# ECG_PWR_MGMT.net
KiCad netlist of a schematic drawn in Altium Designer
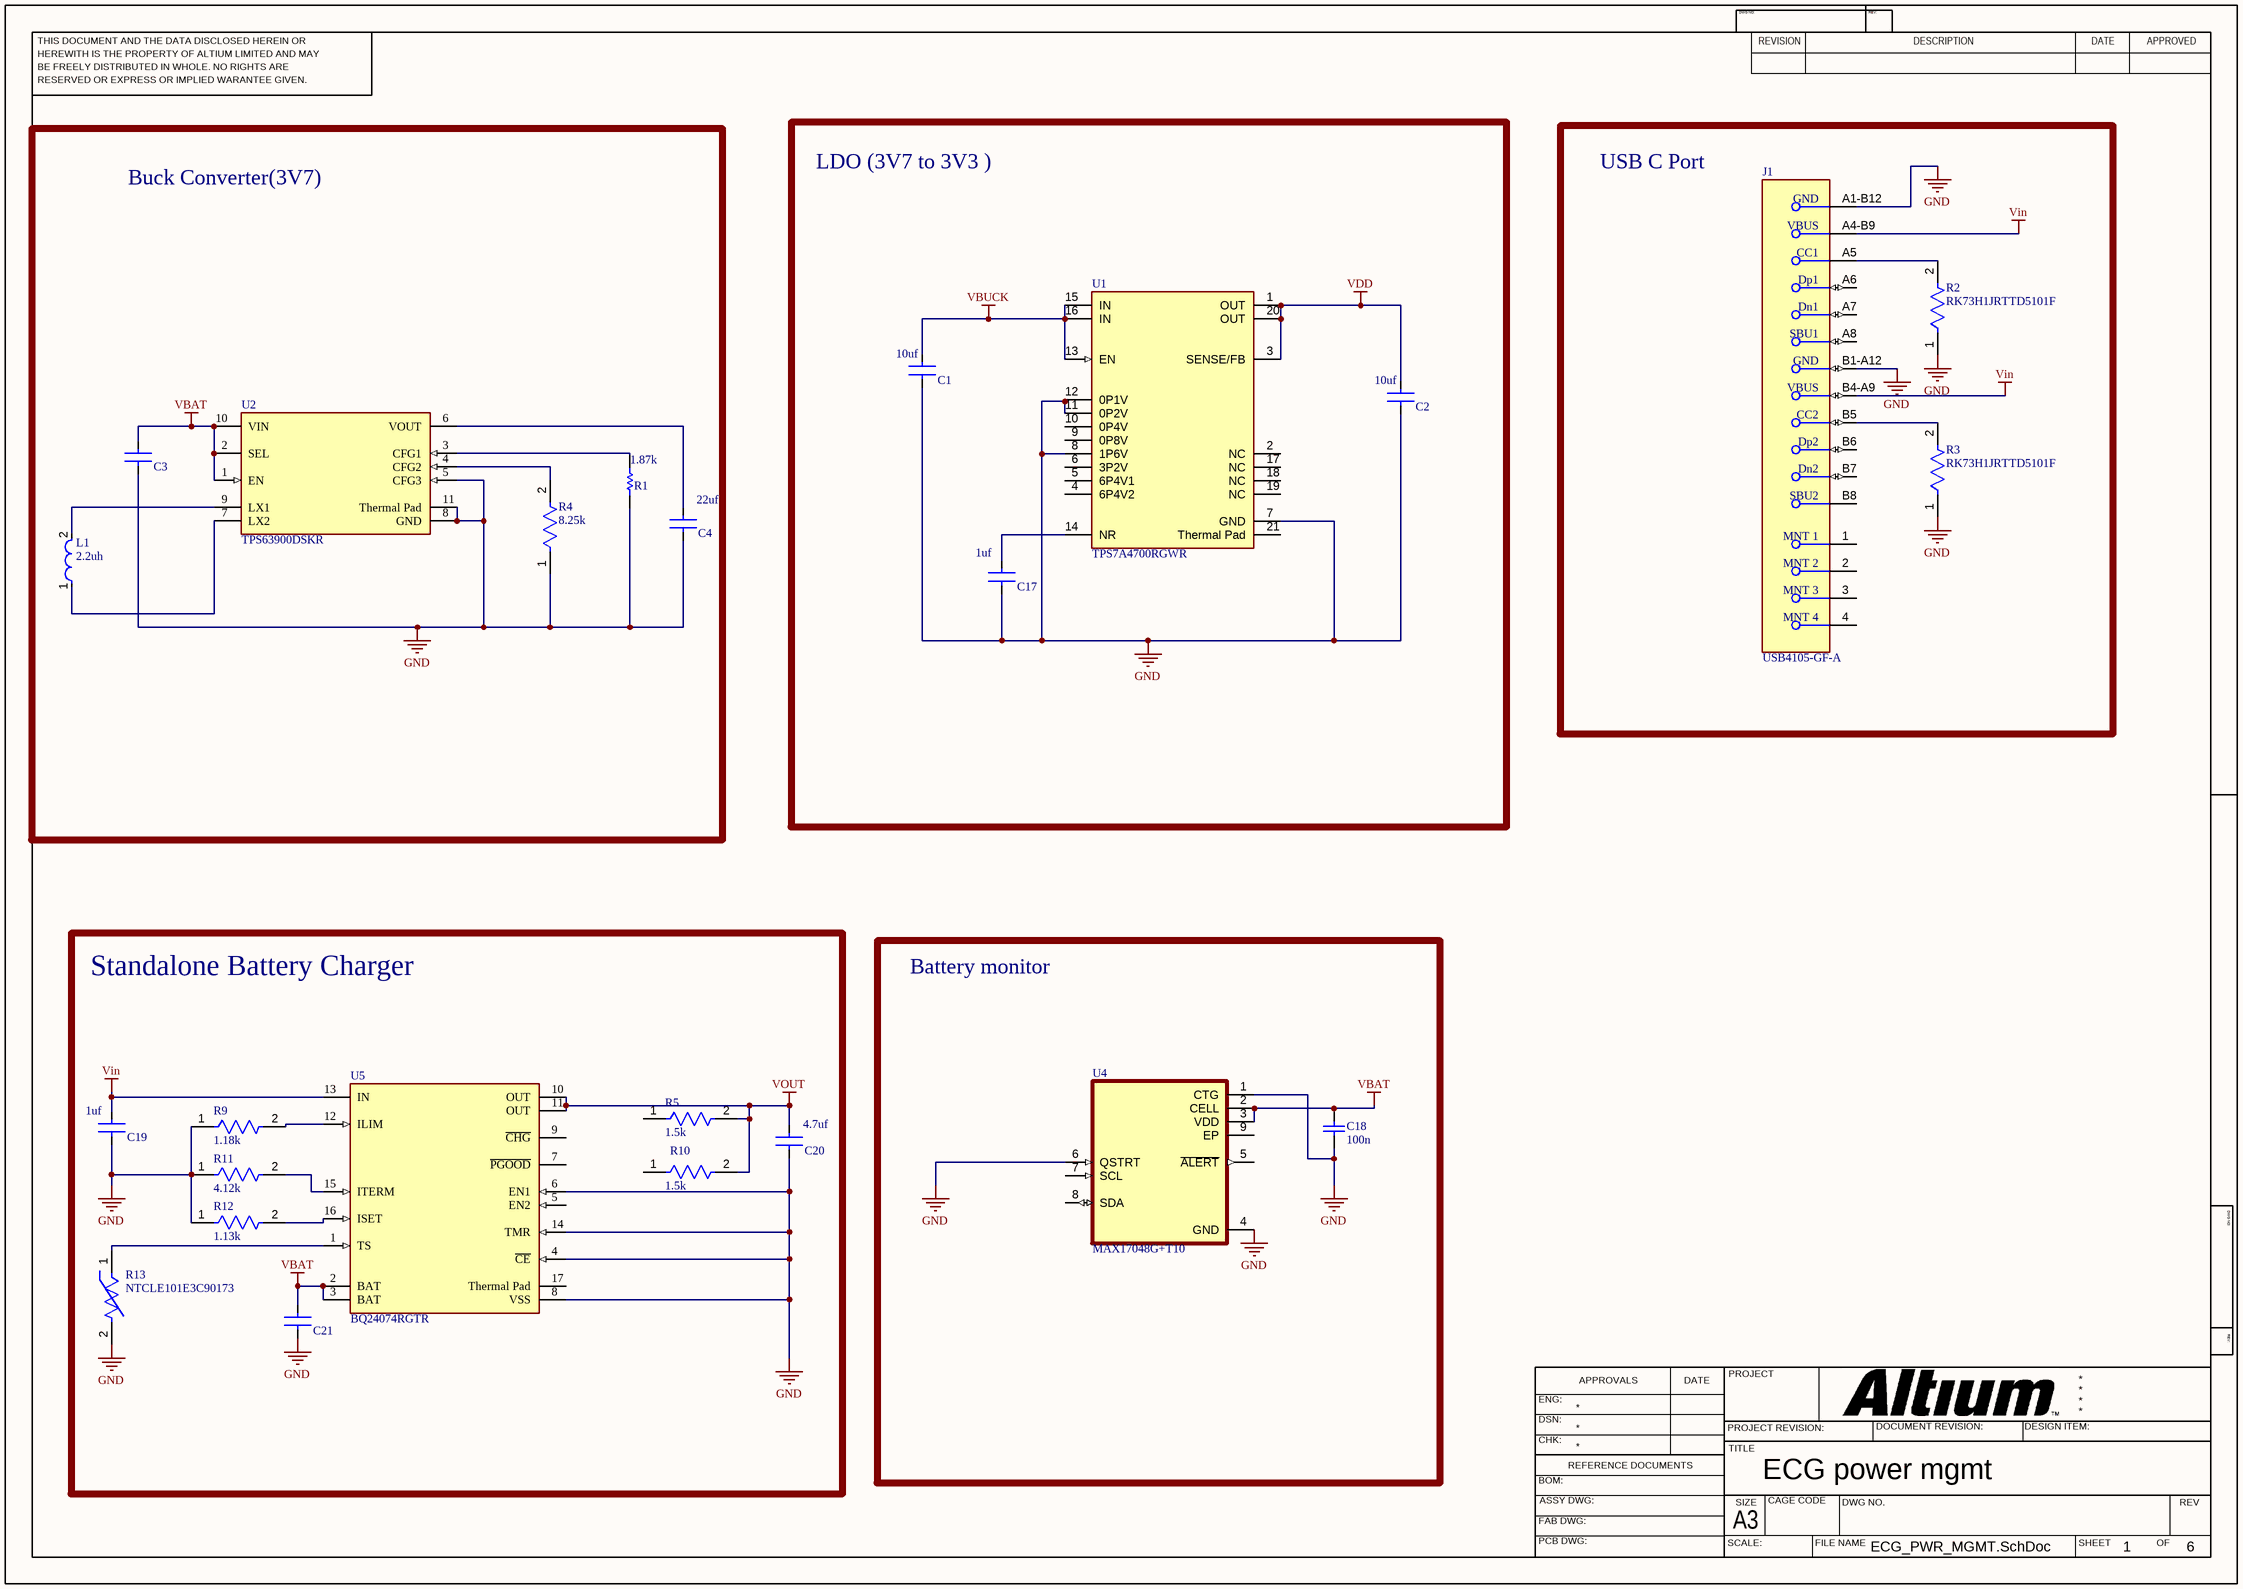
[diagram p0: ECG_PWR_MGMT.SchDoc]

(export (version "E")
  (design (tool "Eeschema 10.0.6"))
  (components
    (comp (ref "C1") (value "10uf") (libsource (lib "ecg_device_components") (part "CAP-0805-16V-SMD-IPC_A")))
    (comp (ref "C2") (value "10uf") (libsource (lib "ecg_device_components") (part "CAP-0805-16V-SMD-IPC_A")))
    (comp (ref "C3")
      (value "Template for SMD cap")
      (libsource (lib "ecg_device_components") (part "CAP-0805-16V-SMD-IPC_A"))
    )
    (comp (ref "C4") (value "22uf") (libsource (lib "ecg_device_components") (part "CAP-0805-16V-SMD-IPC_A")))
    (comp (ref "C17") (value "1uf") (libsource (lib "ecg_device_components") (part "CAP-0805-16V-SMD-IPC_A")))
    (comp (ref "C18")
      (value "100n")
      (footprint "CAP_SMD_0603_IPC_A")
      (fields
        (field (name "MANUFACTURER") "AVX Interconnect / Elco")
        (field (name "PART NUMBER") "0603ZC103MAT2A")
      )
      (libsource (lib "ecg_device_components") (part "CAP-0603-16V-SMD"))
    )
    (comp (ref "C19") (value "1uf") (libsource (lib "ecg_device_components") (part "CAP-0805-16V-SMD-IPC_A")))
    (comp (ref "C20")
      (value "4.7uf")
      (libsource (lib "ecg_device_components") (part "CAP-0805-16V-SMD-IPC_A"))
    )
    (comp (ref "C21")
      (value "Template for SMD cap")
      (libsource (lib "ecg_device_components") (part "CAP-0805-16V-SMD-IPC_A"))
    )
    (comp (ref "J1")
      (value "USB4105-GF-A")
      (footprint "FP-USB4105-GF-A-MFG")
      (description "CONN RCPT USB2.0 TYPEC 5A")
      (fields
        (field (name "MANUFACTURER") "GCT")
        (field (name "OCTOPART") "https://octopart.com/usb4105-gf-a-gct-106627878")
      )
      (libsource (lib "Altium Content Vault") (part "e7c17a616881a82b79941196b4bec10"))
    )
    (comp (ref "L1")
      (value "2.2uh")
      (footprint "FP-LQM2HPN_G0-IPC_C")
      (description "Multilayer Type Inductor for Power Lines, 1008 (2520), 2.2μH, 20%, 0.1Ω, 1.3A")
      (fields (field (name "TOLERANCE") "20%"))
      (libsource (lib "Altium Content Vault") (part "725321dda6339637d4d059423bc1c3c"))
    )
    (comp (ref "R1")
      (value "1.87k")
      (footprint "RESC2013X60X35ML10T20")
      (libsource (lib "ecg_device_components") (part "1K 0805"))
    )
    (comp (ref "R2")
      (value "RK73H1JRTTD5101F")
      (footprint "FP-RK73H1J-IPC_C")
      (description "5.1kΩ ±1% 0.1W Chip Resistor 0603 Flat Chip (Anti-Sulfuration) AEC-Q200 Qualified")
      (fields (field (name "TOLERANCE") "1%"))
      (libsource (lib "Altium Content Vault") (part "1029c3af85768c4190bb7ad29bc67b5"))
    )
    (comp (ref "R3")
      (value "RK73H1JRTTD5101F")
      (footprint "FP-RK73H1J-IPC_C")
      (description "5.1kΩ ±1% 0.1W Chip Resistor 0603 Flat Chip (Anti-Sulfuration) AEC-Q200 Qualified")
      (fields (field (name "TOLERANCE") "1%"))
      (libsource (lib "Altium Content Vault") (part "1029c3af85768c4190bb7ad29bc67b5"))
    )
    (comp (ref "R4")
      (value "8.25k")
      (footprint "FP-MCT0603-IPC_B")
      (description "RES SMD 100 OHM 1% 1/8W 0603")
      (libsource (lib "Altium Content Vault") (part "1029c3af85768c4190bb7ad29bc67b5"))
    )
    (comp (ref "R5")
      (value "1.5k")
      (footprint "FP-MCT0603-IPC_B")
      (description "RES SMD 100 OHM 1% 1/8W 0603")
      (libsource (lib "Altium Content Vault") (part "1029c3af85768c4190bb7ad29bc67b5"))
    )
    (comp (ref "R9")
      (value "1.18k")
      (footprint "FP-MCT0603-IPC_B")
      (description "RES SMD 100 OHM 1% 1/8W 0603")
      (libsource (lib "Altium Content Vault") (part "1029c3af85768c4190bb7ad29bc67b5"))
    )
    (comp (ref "R10")
      (value "1.5k")
      (footprint "FP-MCT0603-IPC_B")
      (description "RES SMD 100 OHM 1% 1/8W 0603")
      (libsource (lib "Altium Content Vault") (part "1029c3af85768c4190bb7ad29bc67b5"))
    )
    (comp (ref "R11")
      (value "4.12k")
      (footprint "FP-MCT0603-IPC_B")
      (description "RES SMD 100 OHM 1% 1/8W 0603")
      (libsource (lib "Altium Content Vault") (part "1029c3af85768c4190bb7ad29bc67b5"))
    )
    (comp (ref "R12")
      (value "1.13k")
      (footprint "FP-MCT0603-IPC_B")
      (description "RES SMD 100 OHM 1% 1/8W 0603")
      (libsource (lib "Altium Content Vault") (part "1029c3af85768c4190bb7ad29bc67b5"))
    )
    (comp (ref "R13")
      (value "NTCLE101E3C90173")
      (footprint "FP-NTCLE101E3C90173-MFG")
      (description "THERM NTC 10KOHM 3435K RADIAL")
      (fields (field (name "TOLERANCE") "1%"))
      (libsource (lib "Altium Content Vault") (part "3b148a6ebabc5fb4d708a66c052d352"))
    )
    (comp (ref "U1")
      (value "TPS7A4700RGWR")
      (footprint "FP-RGW0020A-MFG")
      (description "IC REG LINEAR POS ADJ 1A 20VQFN")
      (fields
        (field (name "OCTOPART") "https://octopart.com/tps7a4700rgwr-texas+instruments-21221956")
        (field (name "MANUFACTURER") "Texas Instruments")
      )
      (libsource (lib "Altium Content Vault") (part "8e99b082ac9f85253ef2256b190b767"))
    )
    (comp (ref "U2")
      (value "TPS63900DSKR")
      (footprint "FP-DSK0010A-IPC_C")
      (description "1.8-V TO 5.5-V, 75-NA IQ BUCK-BO")
      (libsource (lib "Altium Content Vault") (part "087cbe63ebfe39a16d3bf11a348b5dd"))
    )
    (comp (ref "U4")
      (value "MAX17048G+T10")
      (footprint "max17048g+t10")
      (description "3ÂµA 1-Cell/2-Cell Fuel Gauge with ModelGauge")
      (fields (field (name "MF") "Analog Devices"))
      (libsource (lib "ecg_device_components") (part "MAX17048G+T10"))
    )
    (comp (ref "U5")
      (value "BQ24074RGTR")
      (footprint "FP-RGT0016C-IPC_B")
      (description "IC LI-ION CHARGE MGMT 16-QFN")
      (libsource (lib "Altium Content Vault") (part "bc0294d1c007ba64400ebcffad863a1"))
    )
  )
  (nets
    (net (code "1") (name "GND") (class "Default")
      (node (ref "C1") (pin "1") (pinfunction "1_1") (pintype "passive"))
      (node (ref "C17") (pin "1") (pinfunction "1_1") (pintype "passive"))
      (node (ref "C18") (pin "1") (pinfunction "1_1") (pintype "passive"))
      (node (ref "C19") (pin "1") (pinfunction "1_1") (pintype "passive"))
      (node (ref "C2") (pin "1") (pinfunction "1_1") (pintype "passive"))
      (node (ref "C20") (pin "1") (pinfunction "1_1") (pintype "passive"))
      (node (ref "C21") (pin "1") (pinfunction "1_1") (pintype "passive"))
      (node (ref "C3") (pin "1") (pinfunction "1_1") (pintype "passive"))
      (node (ref "C4") (pin "1") (pinfunction "1_1") (pintype "passive"))
      (node (ref "J1") (pin "A1-B12") (pinfunction "GND_A1-B12") (pintype "power_in"))
      (node (ref "J1") (pin "B1-A12") (pinfunction "GND_B1-A12") (pintype "bidirectional"))
      (node (ref "R1") (pin "1") (pinfunction "1_1") (pintype "passive"))
      (node (ref "R11") (pin "1") (pinfunction "1_1") (pintype "passive"))
      (node (ref "R12") (pin "1") (pinfunction "1_1") (pintype "passive"))
      (node (ref "R13") (pin "2") (pinfunction "2_2") (pintype "passive"))
      (node (ref "R2") (pin "1") (pinfunction "1_1") (pintype "passive"))
      (node (ref "R3") (pin "1") (pinfunction "1_1") (pintype "passive"))
      (node (ref "R4") (pin "1") (pinfunction "1_1") (pintype "passive"))
      (node (ref "R9") (pin "1") (pinfunction "1_1") (pintype "passive"))
      (node (ref "U1") (pin "11") (pinfunction "0P2V_11") (pintype "passive"))
      (node (ref "U1") (pin "12") (pinfunction "0P1V_12") (pintype "passive"))
      (node (ref "U1") (pin "7") (pinfunction "GND_7") (pintype "power_in"))
      (node (ref "U1") (pin "8") (pinfunction "1P6V_8") (pintype "passive"))
      (node (ref "U2") (pin "11") (pinfunction "Thermal_Pad_11") (pintype "power_in"))
      (node (ref "U2") (pin "5") (pinfunction "CFG3_5") (pintype "input"))
      (node (ref "U2") (pin "8") (pinfunction "GND_8") (pintype "power_in"))
      (node (ref "U4") (pin "1") (pinfunction "CTG_1") (pintype "power_in"))
      (node (ref "U4") (pin "4") (pinfunction "GND_4") (pintype "power_in"))
      (node (ref "U4") (pin "6") (pinfunction "QSTRT_6") (pintype "input"))
      (node (ref "U5") (pin "14") (pinfunction "TMR_14") (pintype "input"))
      (node (ref "U5") (pin "4") (pinfunction "~{CE}_4") (pintype "input"))
      (node (ref "U5") (pin "6") (pinfunction "EN1_6") (pintype "input"))
      (node (ref "U5") (pin "8") (pinfunction "VSS_8") (pintype "power_in"))
    )
    (net (code "2") (name "Net-(J1-CC1)") (class "Default")
      (node (ref "J1") (pin "A5") (pinfunction "CC1_A5") (pintype "power_in"))
      (node (ref "R2") (pin "2") (pinfunction "2_2") (pintype "passive"))
    )
    (net (code "3") (name "Net-(J1-CC2)") (class "Default")
      (node (ref "J1") (pin "B5") (pinfunction "CC2_B5") (pintype "bidirectional"))
      (node (ref "R3") (pin "2") (pinfunction "2_2") (pintype "passive"))
    )
    (net (code "4") (name "Net-(U1-NR)") (class "Default")
      (node (ref "C17") (pin "2") (pinfunction "2_2") (pintype "passive"))
      (node (ref "U1") (pin "14") (pinfunction "NR_14") (pintype "passive"))
    )
    (net (code "5") (name "Net-(U2-CFG1)") (class "Default")
      (node (ref "R1") (pin "2") (pinfunction "2_2") (pintype "passive"))
      (node (ref "U2") (pin "3") (pinfunction "CFG1_3") (pintype "input"))
    )
    (net (code "6") (name "Net-(U2-CFG2)") (class "Default")
      (node (ref "R4") (pin "2") (pinfunction "2_2") (pintype "passive"))
      (node (ref "U2") (pin "4") (pinfunction "CFG2_4") (pintype "input"))
    )
    (net (code "7") (name "Net-(U2-LX1)") (class "Default")
      (node (ref "L1") (pin "2") (pinfunction "2_2") (pintype "passive"))
      (node (ref "U2") (pin "9") (pinfunction "LX1_9") (pintype "passive"))
    )
    (net (code "8") (name "Net-(U2-LX2)") (class "Default")
      (node (ref "L1") (pin "1") (pinfunction "1_1") (pintype "passive"))
      (node (ref "U2") (pin "7") (pinfunction "LX2_7") (pintype "passive"))
    )
    (net (code "9") (name "Net-(U2-VOUT)") (class "Default")
      (node (ref "C4") (pin "2") (pinfunction "2_2") (pintype "passive"))
      (node (ref "U2") (pin "6") (pinfunction "VOUT_6") (pintype "passive"))
    )
    (net (code "10") (name "Net-(U5-ILIM)") (class "Default")
      (node (ref "R9") (pin "2") (pinfunction "2_2") (pintype "passive"))
      (node (ref "U5") (pin "12") (pinfunction "ILIM_12") (pintype "input"))
    )
    (net (code "11") (name "Net-(U5-ISET)") (class "Default")
      (node (ref "R12") (pin "2") (pinfunction "2_2") (pintype "passive"))
      (node (ref "U5") (pin "16") (pinfunction "ISET_16") (pintype "input"))
    )
    (net (code "12") (name "Net-(U5-ITERM)") (class "Default")
      (node (ref "R11") (pin "2") (pinfunction "2_2") (pintype "passive"))
      (node (ref "U5") (pin "15") (pinfunction "ITERM_15") (pintype "input"))
    )
    (net (code "13") (name "Net-(U5-TS)") (class "Default")
      (node (ref "R13") (pin "1") (pinfunction "1_1") (pintype "passive"))
      (node (ref "U5") (pin "1") (pinfunction "TS_1") (pintype "input"))
    )
    (net (code "14") (name "VBAT") (class "Default")
      (node (ref "C18") (pin "2") (pinfunction "2_2") (pintype "passive"))
      (node (ref "C21") (pin "2") (pinfunction "2_2") (pintype "passive"))
      (node (ref "C3") (pin "2") (pinfunction "2_2") (pintype "passive"))
      (node (ref "U2") (pin "1") (pinfunction "EN_1") (pintype "input"))
      (node (ref "U2") (pin "10") (pinfunction "VIN_10") (pintype "power_in"))
      (node (ref "U2") (pin "2") (pinfunction "SEL_2") (pintype "passive"))
      (node (ref "U4") (pin "2") (pinfunction "CELL_2") (pintype "power_in"))
      (node (ref "U4") (pin "3") (pinfunction "VDD_3") (pintype "power_in"))
      (node (ref "U5") (pin "2") (pinfunction "BAT_2") (pintype "power_in"))
      (node (ref "U5") (pin "3") (pinfunction "BAT_3") (pintype "power_in"))
    )
    (net (code "15") (name "VBUCK") (class "Default")
      (node (ref "C1") (pin "2") (pinfunction "2_2") (pintype "passive"))
      (node (ref "U1") (pin "13") (pinfunction "EN_13") (pintype "input"))
      (node (ref "U1") (pin "15") (pinfunction "IN_15") (pintype "power_in"))
      (node (ref "U1") (pin "16") (pinfunction "IN_16") (pintype "power_in"))
    )
    (net (code "16") (name "VDD") (class "Default")
      (node (ref "C2") (pin "2") (pinfunction "2_2") (pintype "passive"))
      (node (ref "U1") (pin "1") (pinfunction "OUT_1") (pintype "power_in"))
      (node (ref "U1") (pin "20") (pinfunction "OUT_20") (pintype "power_in"))
      (node (ref "U1") (pin "3") (pinfunction "SENSE/FB_3") (pintype "passive"))
    )
    (net (code "17") (name "VOUT") (class "Default")
      (node (ref "C20") (pin "2") (pinfunction "2_2") (pintype "passive"))
      (node (ref "R10") (pin "2") (pinfunction "2_2") (pintype "passive"))
      (node (ref "R5") (pin "2") (pinfunction "2_2") (pintype "passive"))
      (node (ref "U5") (pin "10") (pinfunction "OUT_10") (pintype "power_in"))
      (node (ref "U5") (pin "11") (pinfunction "OUT_11") (pintype "power_in"))
    )
    (net (code "18") (name "Vin") (class "Default")
      (node (ref "C19") (pin "2") (pinfunction "2_2") (pintype "passive"))
      (node (ref "J1") (pin "A4-B9") (pinfunction "VBUS_A4-B9") (pintype "power_in"))
      (node (ref "J1") (pin "B4-A9") (pinfunction "VBUS_B4-A9") (pintype "bidirectional"))
      (node (ref "U5") (pin "13") (pinfunction "IN_13") (pintype "power_in"))
    )
    (net (code "19") (name "unconnected-(J1-Dn1-PadA7)") (class "Default")
      (node (ref "J1") (pin "A7") (pinfunction "Dn1_A7") (pintype "bidirectional"))
    )
    (net (code "20") (name "unconnected-(J1-Dn2-PadB7)") (class "Default")
      (node (ref "J1") (pin "B7") (pinfunction "Dn2_B7") (pintype "bidirectional"))
    )
    (net (code "21") (name "unconnected-(J1-Dp1-PadA6)") (class "Default")
      (node (ref "J1") (pin "A6") (pinfunction "Dp1_A6") (pintype "bidirectional"))
    )
    (net (code "22") (name "unconnected-(J1-Dp2-PadB6)") (class "Default")
      (node (ref "J1") (pin "B6") (pinfunction "Dp2_B6") (pintype "bidirectional"))
    )
    (net (code "23") (name "unconnected-(J1-MNT_1-Pad1)") (class "Default")
      (node (ref "J1") (pin "1") (pinfunction "MNT_1_1") (pintype "power_in"))
    )
    (net (code "24") (name "unconnected-(J1-MNT_2-Pad2)") (class "Default")
      (node (ref "J1") (pin "2") (pinfunction "MNT_2_2") (pintype "power_in"))
    )
    (net (code "25") (name "unconnected-(J1-MNT_3-Pad3)") (class "Default")
      (node (ref "J1") (pin "3") (pinfunction "MNT_3_3") (pintype "power_in"))
    )
    (net (code "26") (name "unconnected-(J1-MNT_4-Pad4)") (class "Default")
      (node (ref "J1") (pin "4") (pinfunction "MNT_4_4") (pintype "power_in"))
    )
    (net (code "27") (name "unconnected-(J1-SBU1-PadA8)") (class "Default")
      (node (ref "J1") (pin "A8") (pinfunction "SBU1_A8") (pintype "bidirectional"))
    )
    (net (code "28") (name "unconnected-(J1-SBU2-PadB8)") (class "Default")
      (node (ref "J1") (pin "B8") (pinfunction "SBU2_B8") (pintype "power_in"))
    )
    (net (code "29") (name "unconnected-(R5-Pad1)") (class "Default")
      (node (ref "R5") (pin "1") (pinfunction "1_1") (pintype "passive"))
    )
    (net (code "30") (name "unconnected-(R10-Pad1)") (class "Default")
      (node (ref "R10") (pin "1") (pinfunction "1_1") (pintype "passive"))
    )
    (net (code "31") (name "unconnected-(U1-0P4V-Pad10)") (class "Default")
      (node (ref "U1") (pin "10") (pinfunction "0P4V_10") (pintype "passive"))
    )
    (net (code "32") (name "unconnected-(U1-0P8V-Pad9)") (class "Default")
      (node (ref "U1") (pin "9") (pinfunction "0P8V_9") (pintype "passive"))
    )
    (net (code "33") (name "unconnected-(U1-3P2V-Pad6)") (class "Default")
      (node (ref "U1") (pin "6") (pinfunction "3P2V_6") (pintype "passive"))
    )
    (net (code "34") (name "unconnected-(U1-6P4V1-Pad5)") (class "Default")
      (node (ref "U1") (pin "5") (pinfunction "6P4V1_5") (pintype "passive"))
    )
    (net (code "35") (name "unconnected-(U1-6P4V2-Pad4)") (class "Default")
      (node (ref "U1") (pin "4") (pinfunction "6P4V2_4") (pintype "passive"))
    )
    (net (code "36") (name "unconnected-(U1-NC-Pad2)") (class "Default")
      (node (ref "U1") (pin "2") (pinfunction "NC_2") (pintype "passive"))
    )
    (net (code "37") (name "unconnected-(U1-NC-Pad17)") (class "Default")
      (node (ref "U1") (pin "17") (pinfunction "NC_17") (pintype "passive"))
    )
    (net (code "38") (name "unconnected-(U1-NC-Pad18)") (class "Default")
      (node (ref "U1") (pin "18") (pinfunction "NC_18") (pintype "passive"))
    )
    (net (code "39") (name "unconnected-(U1-NC-Pad19)") (class "Default")
      (node (ref "U1") (pin "19") (pinfunction "NC_19") (pintype "passive"))
    )
    (net (code "40") (name "unconnected-(U1-Thermal_Pad-Pad21)") (class "Default")
      (node (ref "U1") (pin "21") (pinfunction "Thermal_Pad_21") (pintype "power_in"))
    )
    (net (code "41") (name "unconnected-(U4-EP-Pad9)") (class "Default")
      (node (ref "U4") (pin "9") (pinfunction "EP_9") (pintype "power_in"))
    )
    (net (code "42") (name "unconnected-(U4-SCL-Pad7)") (class "Default")
      (node (ref "U4") (pin "7") (pinfunction "SCL_7") (pintype "input"))
    )
    (net (code "43") (name "unconnected-(U4-SDA-Pad8)") (class "Default")
      (node (ref "U4") (pin "8") (pinfunction "SDA_8") (pintype "bidirectional"))
    )
    (net (code "44") (name "unconnected-(U4-~{ALERT}-Pad5)") (class "Default")
      (node (ref "U4") (pin "5") (pinfunction "~{ALERT}_5") (pintype "output"))
    )
    (net (code "45") (name "unconnected-(U5-EN2-Pad5)") (class "Default")
      (node (ref "U5") (pin "5") (pinfunction "EN2_5") (pintype "input"))
    )
    (net (code "46") (name "unconnected-(U5-Thermal_Pad-Pad17)") (class "Default")
      (node (ref "U5") (pin "17") (pinfunction "Thermal_Pad_17") (pintype "power_in"))
    )
    (net (code "47") (name "unconnected-(U5-~{CHG}-Pad9)") (class "Default")
      (node (ref "U5") (pin "9") (pinfunction "~{CHG}_9") (pintype "tri_state"))
    )
    (net (code "48") (name "unconnected-(U5-~{PGOOD}-Pad7)") (class "Default")
      (node (ref "U5") (pin "7") (pinfunction "~{PGOOD}_7") (pintype "tri_state"))
    )
  )
)
